# Breakout_UVA.net
KiCad netlist of a schematic drawn in EAGLE
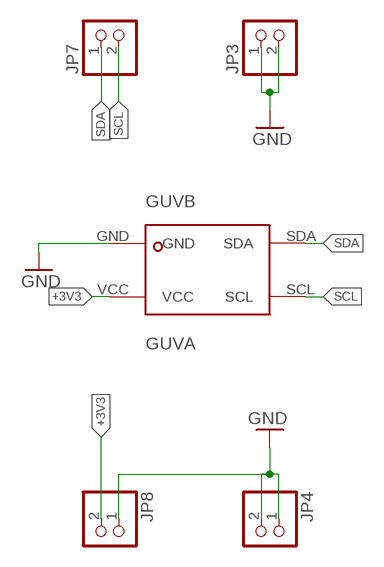
[diagram p0: schematic, sheet 1]

(export (version "E")
  (design (tool "Eeschema 10.0.6"))
  (components
    (comp (ref "GUVB")
      (value "GUVA")
      (footprint "eagle-import:GUV_A_B")
      (libsource (lib "eagle-import") (part "GUVA-C32SM"))
    )
    (comp (ref "JP3")
      (value "PINHD-1X2")
      (footprint "eagle-import:1X02(PAD_REDUZIDO)")
      (libsource (lib "eagle-import") (part "PINHD-1X2"))
    )
    (comp (ref "JP4")
      (value "PINHD-1X2")
      (footprint "eagle-import:1X02(PAD_REDUZIDO)")
      (libsource (lib "eagle-import") (part "PINHD-1X2"))
    )
    (comp (ref "JP7")
      (value "PINHD-1X2")
      (footprint "eagle-import:1X02(PAD_REDUZIDO)")
      (libsource (lib "eagle-import") (part "PINHD-1X2"))
    )
    (comp (ref "JP8")
      (value "PINHD-1X2")
      (footprint "eagle-import:1X02(PAD_REDUZIDO)")
      (libsource (lib "eagle-import") (part "PINHD-1X2"))
    )
  )
  (nets
    (net (code "1") (name "+3V3") (class "Default")
      (node (ref "GUVB") (pin "VCC") (pinfunction "VCC_VCC") (pintype "bidirectional"))
      (node (ref "JP8") (pin "2") (pinfunction "2_2") (pintype "passive"))
    )
    (net (code "2") (name "GND") (class "Default")
      (node (ref "GUVB") (pin "GND") (pinfunction "GND_GND") (pintype "bidirectional"))
      (node (ref "JP3") (pin "1") (pinfunction "1_1") (pintype "passive"))
      (node (ref "JP3") (pin "2") (pinfunction "2_2") (pintype "passive"))
      (node (ref "JP4") (pin "1") (pinfunction "1_1") (pintype "passive"))
      (node (ref "JP4") (pin "2") (pinfunction "2_2") (pintype "passive"))
      (node (ref "JP8") (pin "1") (pinfunction "1_1") (pintype "passive"))
    )
    (net (code "3") (name "SCL") (class "Default")
      (node (ref "GUVB") (pin "SCL") (pinfunction "SCL_SCL") (pintype "bidirectional"))
      (node (ref "JP7") (pin "2") (pinfunction "2_2") (pintype "passive"))
    )
    (net (code "4") (name "SDA") (class "Default")
      (node (ref "GUVB") (pin "SDA") (pinfunction "SDA_SDA") (pintype "bidirectional"))
      (node (ref "JP7") (pin "1") (pinfunction "1_1") (pintype "passive"))
    )
  )
)
